# 07-modem1.net
KiCad netlist of a schematic drawn in Altium Designer
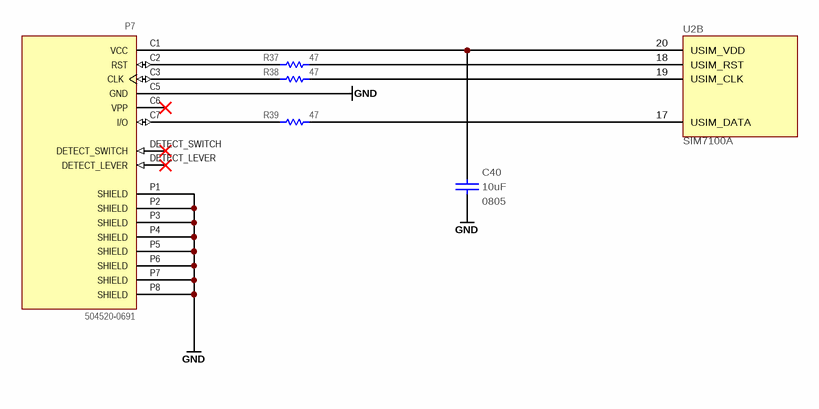
[diagram p0: 07-modem1.SchDoc]

(export (version "E")
  (design (tool "Eeschema 10.0.6"))
  (components
    (comp (ref "C40")
      (value "10uF")
      (footprint "CAPC200X125X145L45N")
      (description "Ceramic Capacitor 10uF ±10% 16V X7R 0805")
      (fields
        (field (name "MANUFACTURER") "Samsung")
        (field (name "TOLERANCE") "±10%")
        (field (name "PACKAGE") "0805")
      )
      (libsource (lib "capacitors") (part "CAP"))
    )
    (comp (ref "P7")
      (value "504520-0691")
      (footprint "504520-0691")
      (description "micro-SIM Card Connector")
      (fields (field (name "MANUFACTURER") "Molex"))
      (libsource (lib "molex") (part "504520-0691"))
    )
    (comp (ref "R37")
      (value "47")
      (footprint "RESC2012X70N")
      (description "Thick Film Resistor 47 ±1% 0805")
      (fields (field (name "MANUFACTURER") "Panasonic") (field (name "TOLERANCE") "±1%"))
      (libsource (lib "Graviton") (part "RES 0402"))
    )
    (comp (ref "R38")
      (value "47")
      (footprint "RESC2012X70N")
      (description "Thick Film Resistor 47 ±1% 0805")
      (fields (field (name "MANUFACTURER") "Panasonic") (field (name "TOLERANCE") "±1%"))
      (libsource (lib "Graviton") (part "RES 0402"))
    )
    (comp (ref "R39")
      (value "47")
      (footprint "RESC2012X70N")
      (description "Thick Film Resistor 47 ±1% 0805")
      (fields (field (name "MANUFACTURER") "Panasonic") (field (name "TOLERANCE") "±1%"))
      (libsource (lib "Graviton") (part "RES 0402"))
    )
    (comp (ref "U2")
      (value "SIM7100A")
      (footprint "SIM7100A")
      (description "Cellular Module")
      (fields (field (name "MANUFACTURER") "SIMCOM"))
      (libsource (lib "simcom") (part "Component_1"))
    )
  )
  (nets
    (net (code "1") (name "GND") (class "Default")
      (node (ref "C40") (pin "2") (pinfunction "2_2") (pintype "passive"))
      (node (ref "P7") (pin "C5") (pinfunction "GND_C5") (pintype "power_in"))
      (node (ref "P7") (pin "P1") (pinfunction "SHIELD_P1") (pintype "passive"))
      (node (ref "P7") (pin "P2") (pinfunction "SHIELD_P2") (pintype "passive"))
      (node (ref "P7") (pin "P3") (pinfunction "SHIELD_P3") (pintype "passive"))
      (node (ref "P7") (pin "P4") (pinfunction "SHIELD_P4") (pintype "passive"))
      (node (ref "P7") (pin "P5") (pinfunction "SHIELD_P5") (pintype "passive"))
      (node (ref "P7") (pin "P6") (pinfunction "SHIELD_P6") (pintype "passive"))
      (node (ref "P7") (pin "P7") (pinfunction "SHIELD_P7") (pintype "passive"))
      (node (ref "P7") (pin "P8") (pinfunction "SHIELD_P8") (pintype "passive"))
    )
    (net (code "2") (name "Net-(P7-CLK)") (class "Default")
      (node (ref "P7") (pin "C3") (pinfunction "CLK_C3") (pintype "bidirectional"))
      (node (ref "R38") (pin "2") (pinfunction "2_2") (pintype "passive"))
    )
    (net (code "3") (name "Net-(P7-I{slash}O)") (class "Default")
      (node (ref "P7") (pin "C7") (pinfunction "I/O_C7") (pintype "bidirectional"))
      (node (ref "R39") (pin "2") (pinfunction "2_2") (pintype "passive"))
    )
    (net (code "4") (name "Net-(P7-RST)") (class "Default")
      (node (ref "P7") (pin "C2") (pinfunction "RST_C2") (pintype "bidirectional"))
      (node (ref "R37") (pin "2") (pinfunction "2_2") (pintype "passive"))
    )
    (net (code "5") (name "Net-(P7-VCC)") (class "Default")
      (node (ref "C40") (pin "1") (pinfunction "1_1") (pintype "passive"))
      (node (ref "P7") (pin "C1") (pinfunction "VCC_C1") (pintype "power_in"))
      (node (ref "U2") (pin "20") (pinfunction "USIM_VDD_20") (pintype "passive"))
    )
    (net (code "6") (name "Net-(U2B-USIM_CLK)") (class "Default")
      (node (ref "R38") (pin "1") (pinfunction "1_1") (pintype "passive"))
      (node (ref "U2") (pin "19") (pinfunction "USIM_CLK_19") (pintype "passive"))
    )
    (net (code "7") (name "Net-(U2B-USIM_DATA)") (class "Default")
      (node (ref "R39") (pin "1") (pinfunction "1_1") (pintype "passive"))
      (node (ref "U2") (pin "17") (pinfunction "USIM_DATA_17") (pintype "passive"))
    )
    (net (code "8") (name "Net-(U2B-USIM_RST)") (class "Default")
      (node (ref "R37") (pin "1") (pinfunction "1_1") (pintype "passive"))
      (node (ref "U2") (pin "18") (pinfunction "USIM_RST_18") (pintype "passive"))
    )
    (net (code "9") (name "unconnected-(P7-PadDETECT_LEVER)") (class "Default")
      (node (ref "P7") (pin "DETECT_LEVER") (pinfunction "DETECT_LEVER_DETECT_LEVER") (pintype "input+no_connect"))
    )
    (net (code "10") (name "unconnected-(P7-PadDETECT_SWITCH)") (class "Default")
      (node (ref "P7") (pin "DETECT_SWITCH") (pinfunction "DETECT_SWITCH_DETECT_SWITCH") (pintype "input+no_connect"))
    )
    (net (code "11") (name "unconnected-(P7-VPP-PadC6)") (class "Default")
      (node (ref "P7") (pin "C6") (pinfunction "VPP_C6") (pintype "power_in+no_connect"))
    )
  )
)
